# HUB75.net
KiCad netlist of a schematic drawn in EAGLE
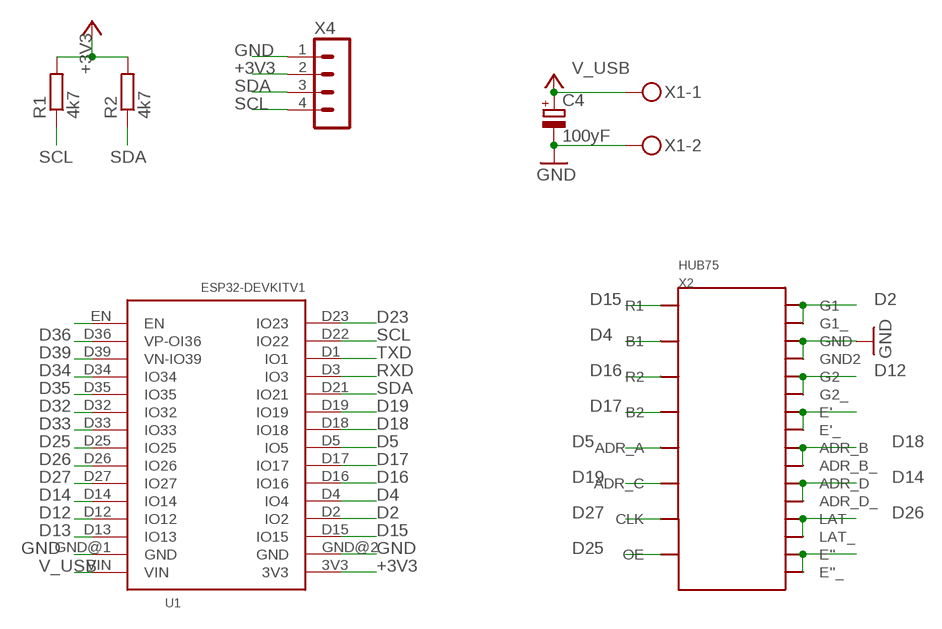
[diagram p0: schematic, sheet 1]

(export (version "E")
  (design (tool "Eeschema 10.0.6"))
  (components
    (comp (ref "C4")
      (value "100yF")
      (footprint "eagle-import:E5-6")
      (libsource (lib "eagle-import") (part "CPOL-EUE5-6"))
    )
    (comp (ref "R1")
      (value "4k7")
      (footprint "eagle-import:R0805")
      (libsource (lib "eagle-import") (part "R-EU_R0805"))
    )
    (comp (ref "R2")
      (value "4k7")
      (footprint "eagle-import:R0805")
      (libsource (lib "eagle-import") (part "R-EU_R0805"))
    )
    (comp (ref "U1")
      (value "ESP32DEVKITV1")
      (footprint "eagle-import:ESP32-DEVKITV1")
      (libsource (lib "eagle-import") (part "ESP32DEVKITV1"))
    )
    (comp (ref "X1")
      (value "MKDSN1,5/2-5,08")
      (footprint "eagle-import:MKDSN1,5_2-5,08")
      (libsource (lib "eagle-import") (part "MKDSN1,5/2-5,08"))
    )
    (comp (ref "X2")
      (value "HUB75")
      (footprint "eagle-import:3X8")
      (libsource (lib "eagle-import") (part "HUB75"))
    )
    (comp (ref "X4")
      (value "B4B-PH-K")
      (footprint "eagle-import:B4B-PH-K")
      (libsource (lib "eagle-import") (part "B4B-PH-K"))
    )
  )
  (nets
    (net (code "1") (name "+3V3") (class "Default")
      (node (ref "R1") (pin "2") (pinfunction "2_2") (pintype "passive"))
      (node (ref "R2") (pin "2") (pinfunction "2_2") (pintype "passive"))
      (node (ref "U1") (pin "3V3") (pinfunction "3V3_3V3") (pintype "bidirectional"))
      (node (ref "X4") (pin "2") (pinfunction "2_2") (pintype "passive"))
    )
    (net (code "2") (name "/D2") (class "Default")
      (node (ref "U1") (pin "D2") (pinfunction "IO2_D2") (pintype "bidirectional"))
      (node (ref "X2") (pin "2") (pinfunction "G1_2") (pintype "bidirectional"))
      (node (ref "X2") (pin "2B") (pinfunction "G1__2B") (pintype "bidirectional"))
    )
    (net (code "3") (name "/D4") (class "Default")
      (node (ref "U1") (pin "D4") (pinfunction "IO4_D4") (pintype "bidirectional"))
      (node (ref "X2") (pin "3") (pinfunction "B1_3") (pintype "bidirectional"))
    )
    (net (code "4") (name "/D5") (class "Default")
      (node (ref "U1") (pin "D5") (pinfunction "IO5_D5") (pintype "bidirectional"))
      (node (ref "X2") (pin "9") (pinfunction "ADR_A_9") (pintype "bidirectional"))
    )
    (net (code "5") (name "/D12") (class "Default")
      (node (ref "U1") (pin "D12") (pinfunction "IO12_D12") (pintype "bidirectional"))
      (node (ref "X2") (pin "6") (pinfunction "G2_6") (pintype "bidirectional"))
      (node (ref "X2") (pin "6B") (pinfunction "G2__6B") (pintype "bidirectional"))
    )
    (net (code "6") (name "/D13") (class "Default")
      (node (ref "U1") (pin "D13") (pinfunction "IO13_D13") (pintype "bidirectional"))
    )
    (net (code "7") (name "/D14") (class "Default")
      (node (ref "U1") (pin "D14") (pinfunction "IO14_D14") (pintype "bidirectional"))
      (node (ref "X2") (pin "12") (pinfunction "ADR_D_12") (pintype "bidirectional"))
      (node (ref "X2") (pin "12B") (pinfunction "ADR_D__12B") (pintype "bidirectional"))
    )
    (net (code "8") (name "/D15") (class "Default")
      (node (ref "U1") (pin "D15") (pinfunction "IO15_D15") (pintype "bidirectional"))
      (node (ref "X2") (pin "1") (pinfunction "R1_1") (pintype "bidirectional"))
    )
    (net (code "9") (name "/D16") (class "Default")
      (node (ref "U1") (pin "D16") (pinfunction "IO16_D16") (pintype "bidirectional"))
      (node (ref "X2") (pin "5") (pinfunction "R2_5") (pintype "bidirectional"))
    )
    (net (code "10") (name "/D17") (class "Default")
      (node (ref "U1") (pin "D17") (pinfunction "IO17_D17") (pintype "bidirectional"))
      (node (ref "X2") (pin "7") (pinfunction "B2_7") (pintype "bidirectional"))
    )
    (net (code "11") (name "/D18") (class "Default")
      (node (ref "U1") (pin "D18") (pinfunction "IO18_D18") (pintype "bidirectional"))
      (node (ref "X2") (pin "10") (pinfunction "ADR_B_10") (pintype "bidirectional"))
      (node (ref "X2") (pin "10B") (pinfunction "ADR_B__10B") (pintype "bidirectional"))
    )
    (net (code "12") (name "/D19") (class "Default")
      (node (ref "U1") (pin "D19") (pinfunction "IO19_D19") (pintype "bidirectional"))
      (node (ref "X2") (pin "11") (pinfunction "ADR_C_11") (pintype "bidirectional"))
    )
    (net (code "13") (name "/D23") (class "Default")
      (node (ref "U1") (pin "D23") (pinfunction "IO23_D23") (pintype "bidirectional"))
    )
    (net (code "14") (name "/D25") (class "Default")
      (node (ref "U1") (pin "D25") (pinfunction "IO25_D25") (pintype "bidirectional"))
      (node (ref "X2") (pin "15") (pinfunction "OE_15") (pintype "bidirectional"))
    )
    (net (code "15") (name "/D26") (class "Default")
      (node (ref "U1") (pin "D26") (pinfunction "IO26_D26") (pintype "bidirectional"))
      (node (ref "X2") (pin "14") (pinfunction "LAT_14") (pintype "bidirectional"))
      (node (ref "X2") (pin "14B") (pinfunction "LAT__14B") (pintype "bidirectional"))
    )
    (net (code "16") (name "/D27") (class "Default")
      (node (ref "U1") (pin "D27") (pinfunction "IO27_D27") (pintype "bidirectional"))
      (node (ref "X2") (pin "13") (pinfunction "CLK_13") (pintype "bidirectional"))
    )
    (net (code "17") (name "/D32") (class "Default")
      (node (ref "U1") (pin "D32") (pinfunction "IO32_D32") (pintype "bidirectional"))
    )
    (net (code "18") (name "/D33") (class "Default")
      (node (ref "U1") (pin "D33") (pinfunction "IO33_D33") (pintype "bidirectional"))
    )
    (net (code "19") (name "/D34") (class "Default")
      (node (ref "U1") (pin "D34") (pinfunction "IO34_D34") (pintype "bidirectional"))
    )
    (net (code "20") (name "/D35") (class "Default")
      (node (ref "U1") (pin "D35") (pinfunction "IO35_D35") (pintype "bidirectional"))
    )
    (net (code "21") (name "/D36") (class "Default")
      (node (ref "U1") (pin "D36") (pinfunction "VP-OI36_D36") (pintype "bidirectional"))
    )
    (net (code "22") (name "/D39") (class "Default")
      (node (ref "U1") (pin "D39") (pinfunction "VN-IO39_D39") (pintype "bidirectional"))
    )
    (net (code "23") (name "/RXD") (class "Default")
      (node (ref "U1") (pin "D3") (pinfunction "IO3_D3") (pintype "bidirectional"))
    )
    (net (code "24") (name "/SCL") (class "Default")
      (node (ref "R1") (pin "1") (pinfunction "1_1") (pintype "passive"))
      (node (ref "U1") (pin "D22") (pinfunction "IO22_D22") (pintype "bidirectional"))
      (node (ref "X4") (pin "4") (pinfunction "4_4") (pintype "passive"))
    )
    (net (code "25") (name "/SDA") (class "Default")
      (node (ref "R2") (pin "1") (pinfunction "1_1") (pintype "passive"))
      (node (ref "U1") (pin "D21") (pinfunction "IO21_D21") (pintype "bidirectional"))
      (node (ref "X4") (pin "3") (pinfunction "3_3") (pintype "passive"))
    )
    (net (code "26") (name "/TXD") (class "Default")
      (node (ref "U1") (pin "D1") (pinfunction "IO1_D1") (pintype "bidirectional"))
    )
    (net (code "27") (name "GND") (class "Default")
      (node (ref "C4") (pin "-") (pinfunction "-_-") (pintype "passive"))
      (node (ref "U1") (pin "GND@1") (pinfunction "GND_GND@1") (pintype "bidirectional"))
      (node (ref "U1") (pin "GND@2") (pinfunction "GND_GND@2") (pintype "bidirectional"))
      (node (ref "X1") (pin "2") (pinfunction "KL_2") (pintype "passive"))
      (node (ref "X2") (pin "4") (pinfunction "GND_4") (pintype "bidirectional"))
      (node (ref "X2") (pin "4B") (pinfunction "GND2_4B") (pintype "bidirectional"))
      (node (ref "X4") (pin "1") (pinfunction "1_1") (pintype "passive"))
    )
    (net (code "28") (name "Net-(X2-E'')") (class "Default")
      (node (ref "X2") (pin "16") (pinfunction "E''_16") (pintype "bidirectional"))
      (node (ref "X2") (pin "16B") (pinfunction "E''__16B") (pintype "bidirectional"))
    )
    (net (code "29") (name "Net-(X2-E')") (class "Default")
      (node (ref "X2") (pin "8") (pinfunction "E'_8") (pintype "bidirectional"))
      (node (ref "X2") (pin "8B") (pinfunction "E'__8B") (pintype "bidirectional"))
    )
    (net (code "30") (name "V+") (class "Default")
      (node (ref "C4") (pin "+") (pinfunction "+_+") (pintype "passive"))
      (node (ref "U1") (pin "VIN") (pinfunction "VIN_VIN") (pintype "bidirectional"))
      (node (ref "X1") (pin "1") (pinfunction "KL_1") (pintype "passive"))
    )
    (net (code "31") (name "unconnected-(U1-PadEN)") (class "Default")
      (node (ref "U1") (pin "EN") (pinfunction "EN_EN") (pintype "bidirectional"))
    )
  )
)
